# FPGA_CFG.net
KiCad netlist of a schematic drawn in Altium Designer
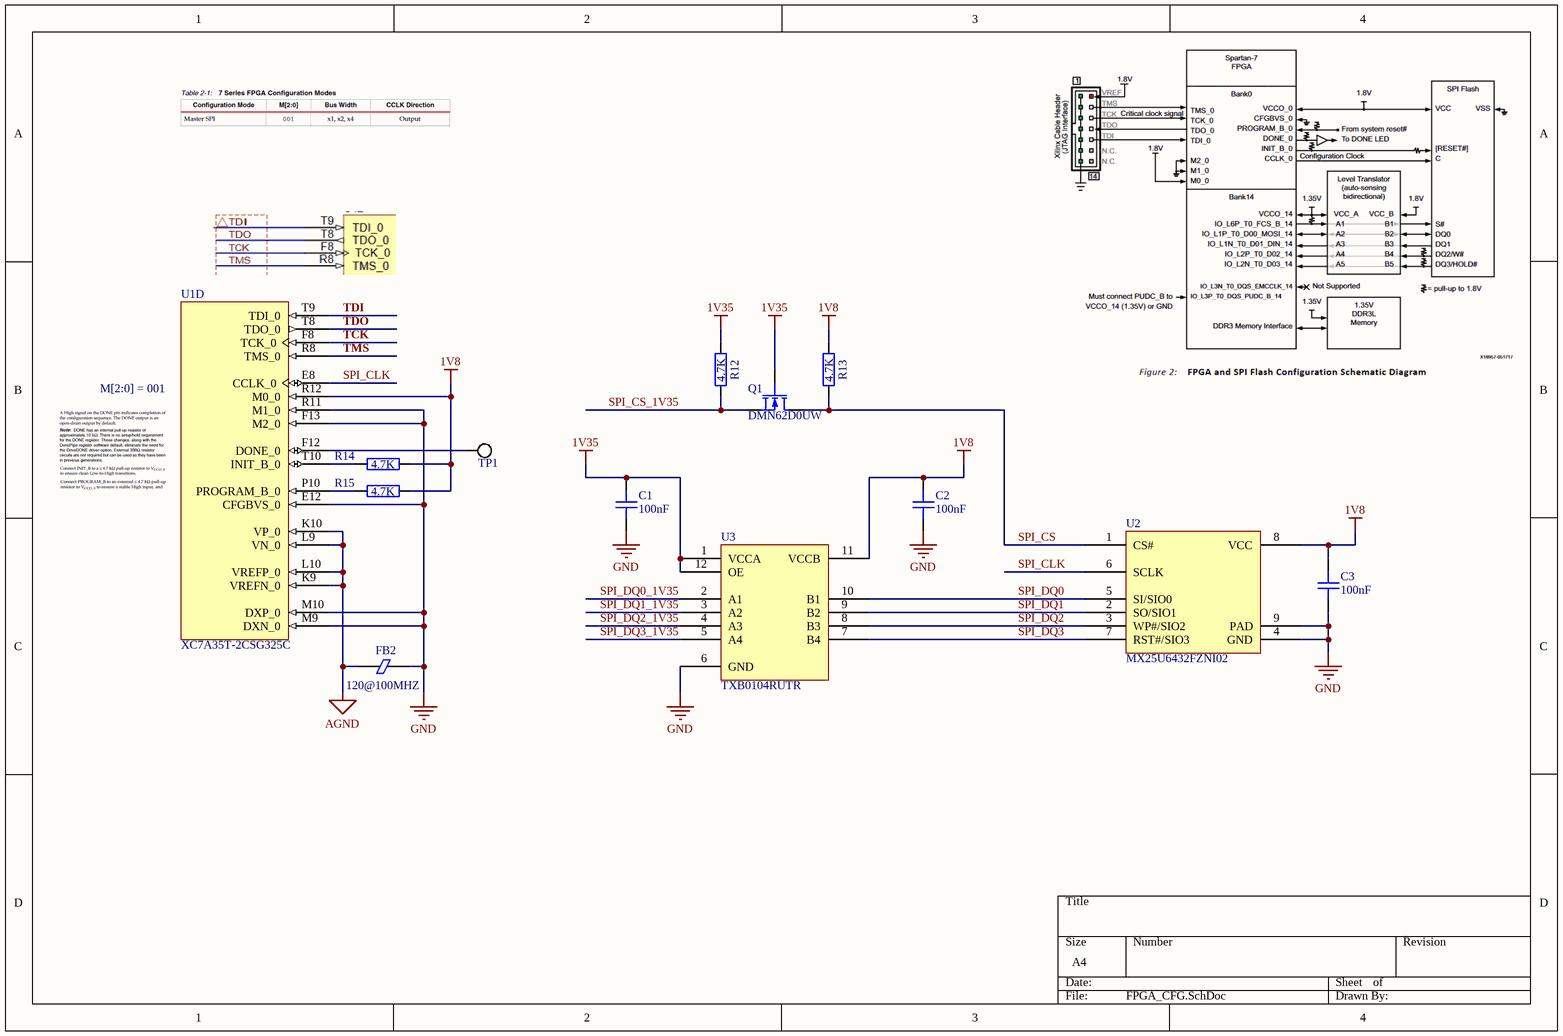
[diagram p0: FPGA_CFG.SchDoc]

(export (version "E")
  (design (tool "Eeschema 10.0.6"))
  (components
    (comp (ref "C1")
      (value "100nF")
      (footprint "GEN_C_0402")
      (libsource (lib "DSO") (part "CAP 100nF 16V X7R 0402"))
    )
    (comp (ref "C2")
      (value "100nF")
      (footprint "GEN_C_0402")
      (libsource (lib "DSO") (part "CAP 100nF 16V X7R 0402"))
    )
    (comp (ref "C3")
      (value "100nF")
      (footprint "GEN_C_0402")
      (libsource (lib "DSO") (part "CAP 100nF 16V X7R 0402"))
    )
    (comp (ref "FB2")
      (value "120@100MHZ")
      (footprint "GEN_R_0402")
      (libsource (lib "DSO") (part "FERRITE BEAD 120 OHM 0402"))
    )
    (comp (ref "Q1")
      (value "DMN62D0UW")
      (footprint "GEN_SOT_323")
      (libsource (lib "DSO") (part "NMOS DMN62D0UW"))
    )
    (comp (ref "R12")
      (value "4.7K")
      (footprint "GEN_R_0201")
      (fields (field (name "TOLERANCE") "1%"))
      (libsource (lib "DSO") (part "RES 4.7K OHM 1% 1/20W 0201"))
    )
    (comp (ref "R13")
      (value "4.7K")
      (footprint "GEN_R_0201")
      (fields (field (name "TOLERANCE") "1%"))
      (libsource (lib "DSO") (part "RES 4.7K OHM 1% 1/20W 0201"))
    )
    (comp (ref "R14")
      (value "4.7K")
      (footprint "GEN_R_0201")
      (fields (field (name "TOLERANCE") "1%"))
      (libsource (lib "") (part "RES 4.7K OHM 1% 1/20W 0201_1"))
    )
    (comp (ref "R15")
      (value "4.7K")
      (footprint "GEN_R_0201")
      (fields (field (name "TOLERANCE") "1%"))
      (libsource (lib "") (part "RES 4.7K OHM 1% 1/20W 0201_1"))
    )
    (comp (ref "TP1") (value "PCB") (footprint "GEN_TP_PCB") (libsource (lib "DSO") (part "TP PCB 1mm")))
    (comp (ref "U1")
      (value "XC7A35T-2CSG325C")
      (footprint "CSG325")
      (description "Artix-7 FPGA, 150 User I/Os, 4 GTP, 324-Ball BGA, Speed Grade 2, Commercial Grade, Pb-Free")
      (fields (field (name "MANUFACTURER") "Xilinx"))
      (libsource (lib "Xilinx Artix-7") (part "XC7A35T-2CSG325C"))
    )
    (comp (ref "U2")
      (value "MX25U6432FZNI02")
      (footprint "MX_WSON8")
      (libsource (lib "DSO") (part "IC FLASH MX25U6432FZNI02"))
    )
    (comp (ref "U3")
      (value "TXB0104RUTR")
      (footprint "TI_UQFN_RUT0012A")
      (libsource (lib "DSO") (part "IC TRNSLTR TXB0104RUTR"))
    )
  )
  (nets
    (net (code "1") (name "/SPI_CLK") (class "Default")
      (node (ref "U1") (pin "E8") (pinfunction "CCLK_0_E8") (pintype "bidirectional"))
      (node (ref "U2") (pin "6") (pinfunction "SCLK_6") (pintype "passive"))
    )
    (net (code "2") (name "/SPI_CS") (class "Default")
      (node (ref "Q1") (pin "1") (pinfunction "D_1") (pintype "passive"))
      (node (ref "R13") (pin "1") (pinfunction "1_1") (pintype "passive"))
      (node (ref "U2") (pin "1") (pinfunction "CS#_1") (pintype "passive"))
    )
    (net (code "3") (name "/SPI_CS_1V35") (class "Default")
      (node (ref "Q1") (pin "3") (pinfunction "S_3") (pintype "passive"))
      (node (ref "R12") (pin "1") (pinfunction "1_1") (pintype "passive"))
    )
    (net (code "4") (name "/SPI_DQ0") (class "Default")
      (node (ref "U2") (pin "5") (pinfunction "SI/SIO0_5") (pintype "passive"))
      (node (ref "U3") (pin "10") (pinfunction "B1_10") (pintype "passive"))
    )
    (net (code "5") (name "/SPI_DQ0_1V35") (class "Default")
      (node (ref "U3") (pin "2") (pinfunction "A1_2") (pintype "passive"))
    )
    (net (code "6") (name "/SPI_DQ1") (class "Default")
      (node (ref "U2") (pin "2") (pinfunction "SO/SIO1_2") (pintype "passive"))
      (node (ref "U3") (pin "9") (pinfunction "B2_9") (pintype "passive"))
    )
    (net (code "7") (name "/SPI_DQ1_1V35") (class "Default")
      (node (ref "U3") (pin "3") (pinfunction "A2_3") (pintype "passive"))
    )
    (net (code "8") (name "/SPI_DQ2") (class "Default")
      (node (ref "U2") (pin "3") (pinfunction "WP#/SIO2_3") (pintype "passive"))
      (node (ref "U3") (pin "8") (pinfunction "B3_8") (pintype "passive"))
    )
    (net (code "9") (name "/SPI_DQ2_1V35") (class "Default")
      (node (ref "U3") (pin "4") (pinfunction "A3_4") (pintype "passive"))
    )
    (net (code "10") (name "/SPI_DQ3") (class "Default")
      (node (ref "U2") (pin "7") (pinfunction "RST#/SIO3_7") (pintype "passive"))
      (node (ref "U3") (pin "7") (pinfunction "B4_7") (pintype "passive"))
    )
    (net (code "11") (name "/SPI_DQ3_1V35") (class "Default")
      (node (ref "U3") (pin "5") (pinfunction "A4_5") (pintype "passive"))
    )
    (net (code "12") (name "/TCK") (class "Default")
      (node (ref "U1") (pin "F8") (pinfunction "TCK_0_F8") (pintype "input"))
    )
    (net (code "13") (name "/TDI") (class "Default")
      (node (ref "U1") (pin "T9") (pinfunction "TDI_0_T9") (pintype "input"))
    )
    (net (code "14") (name "/TDO") (class "Default")
      (node (ref "U1") (pin "T8") (pinfunction "TDO_0_T8") (pintype "output"))
    )
    (net (code "15") (name "/TMS") (class "Default")
      (node (ref "U1") (pin "R8") (pinfunction "TMS_0_R8") (pintype "input"))
    )
    (net (code "16") (name "1V8") (class "Default")
      (node (ref "C2") (pin "1") (pinfunction "1_1") (pintype "passive"))
      (node (ref "C3") (pin "1") (pinfunction "1_1") (pintype "passive"))
      (node (ref "R13") (pin "2") (pinfunction "2_2") (pintype "passive"))
      (node (ref "R14") (pin "2") (pinfunction "2_2") (pintype "passive"))
      (node (ref "R15") (pin "2") (pinfunction "2_2") (pintype "passive"))
      (node (ref "U1") (pin "R12") (pinfunction "M0_0_R12") (pintype "input"))
      (node (ref "U2") (pin "8") (pinfunction "VCC_8") (pintype "passive"))
      (node (ref "U3") (pin "11") (pinfunction "VCCB_11") (pintype "passive"))
    )
    (net (code "17") (name "1V35") (class "Default")
      (node (ref "C1") (pin "1") (pinfunction "1_1") (pintype "passive"))
      (node (ref "Q1") (pin "2") (pinfunction "G_2") (pintype "passive"))
      (node (ref "R12") (pin "2") (pinfunction "2_2") (pintype "passive"))
      (node (ref "U3") (pin "1") (pinfunction "VCCA_1") (pintype "passive"))
      (node (ref "U3") (pin "12") (pinfunction "OE_12") (pintype "passive"))
    )
    (net (code "18") (name "AGND") (class "Default")
      (node (ref "FB2") (pin "1") (pinfunction "1_1") (pintype "passive"))
      (node (ref "U1") (pin "K10") (pinfunction "VP_0_K10") (pintype "input"))
      (node (ref "U1") (pin "K9") (pinfunction "VREFN_0_K9") (pintype "input"))
      (node (ref "U1") (pin "L10") (pinfunction "VREFP_0_L10") (pintype "input"))
      (node (ref "U1") (pin "L9") (pinfunction "VN_0_L9") (pintype "input"))
    )
    (net (code "19") (name "GND") (class "Default")
      (node (ref "C1") (pin "2") (pinfunction "2_2") (pintype "passive"))
      (node (ref "C2") (pin "2") (pinfunction "2_2") (pintype "passive"))
      (node (ref "C3") (pin "2") (pinfunction "2_2") (pintype "passive"))
      (node (ref "FB2") (pin "2") (pinfunction "2_2") (pintype "passive"))
      (node (ref "U1") (pin "E12") (pinfunction "CFGBVS_0_E12") (pintype "input"))
      (node (ref "U1") (pin "F13") (pinfunction "M2_0_F13") (pintype "input"))
      (node (ref "U1") (pin "M10") (pinfunction "DXP_0_M10") (pintype "input"))
      (node (ref "U1") (pin "M9") (pinfunction "DXN_0_M9") (pintype "input"))
      (node (ref "U1") (pin "R11") (pinfunction "M1_0_R11") (pintype "input"))
      (node (ref "U2") (pin "4") (pinfunction "GND_4") (pintype "passive"))
      (node (ref "U2") (pin "9") (pinfunction "PAD_9") (pintype "passive"))
      (node (ref "U3") (pin "6") (pinfunction "GND_6") (pintype "passive"))
    )
    (net (code "20") (name "Net-(U1D-DONE_0)") (class "Default")
      (node (ref "TP1") (pin "1") (pinfunction "1_1") (pintype "passive"))
      (node (ref "U1") (pin "F12") (pinfunction "DONE_0_F12") (pintype "bidirectional"))
    )
    (net (code "21") (name "Net-(U1D-INIT_B_0)") (class "Default")
      (node (ref "R14") (pin "1") (pinfunction "1_1") (pintype "passive"))
      (node (ref "U1") (pin "T10") (pinfunction "INIT_B_0_T10") (pintype "bidirectional"))
    )
    (net (code "22") (name "Net-(U1D-PROGRAM_B_0)") (class "Default")
      (node (ref "R15") (pin "1") (pinfunction "1_1") (pintype "passive"))
      (node (ref "U1") (pin "P10") (pinfunction "PROGRAM_B_0_P10") (pintype "input"))
    )
  )
)
